# PCB.net
KiCad netlist of a schematic drawn in EAGLE
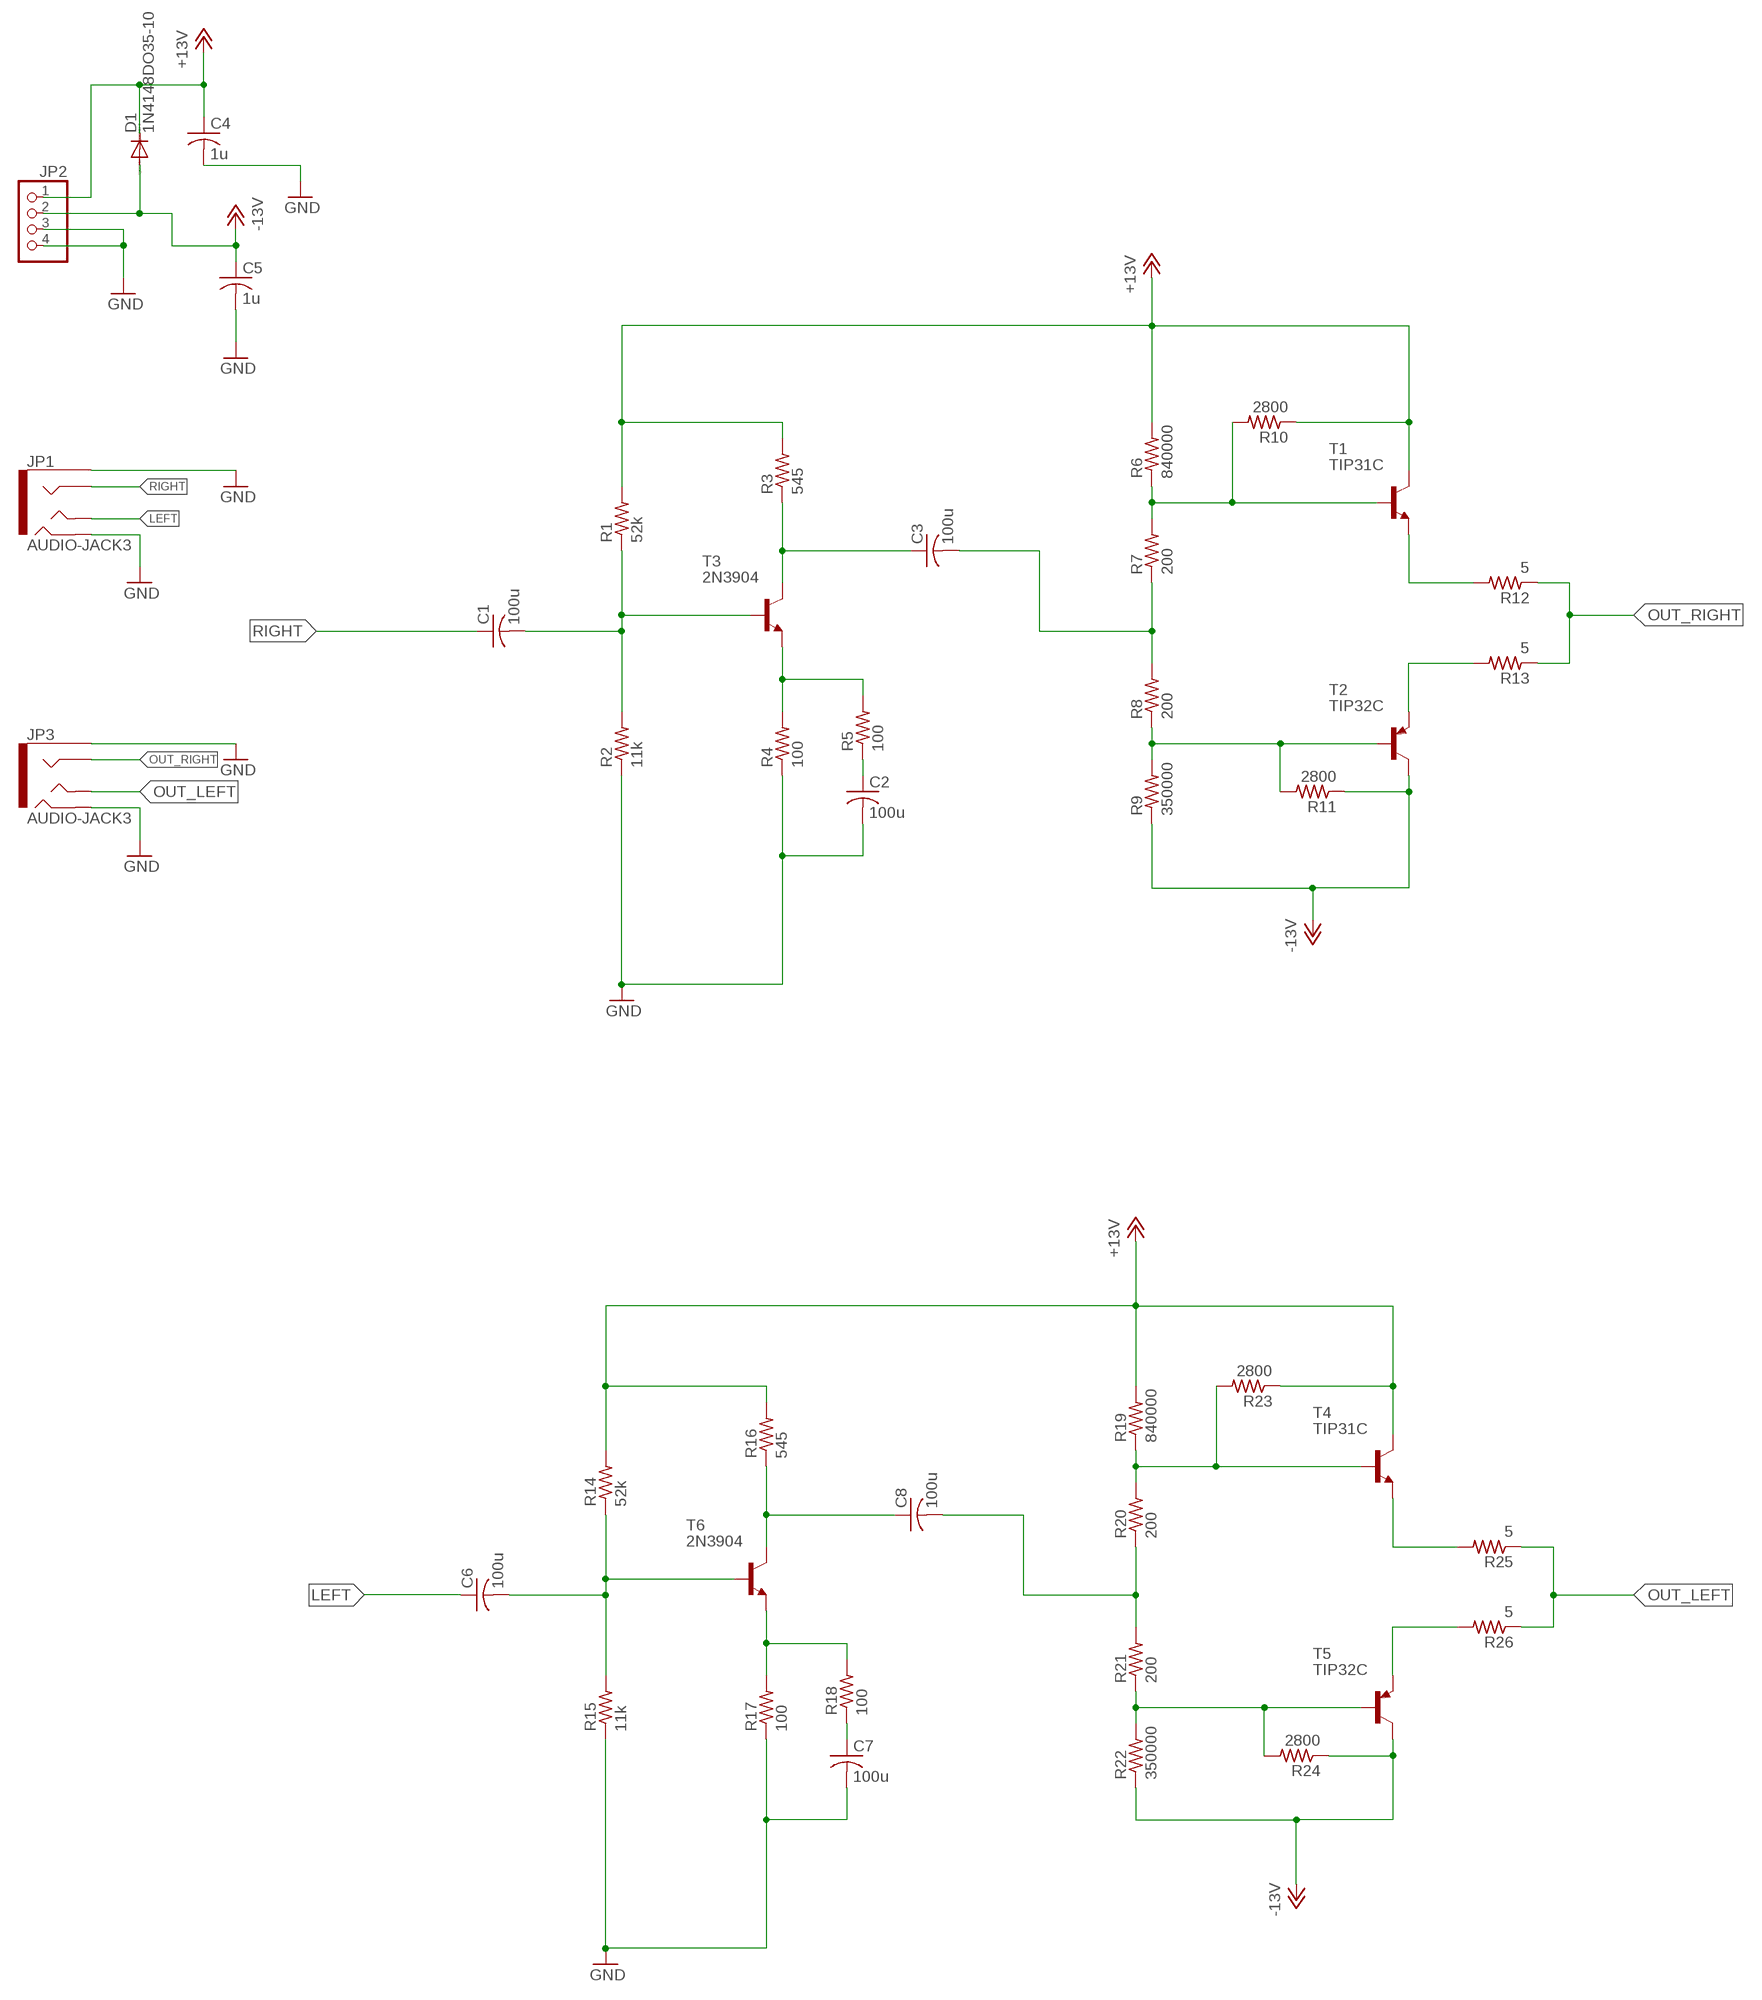
[diagram p0: schematic, sheet 1]

(export (version "E")
  (design (tool "Eeschema 10.0.6"))
  (components
    (comp (ref "C1")
      (value "100u")
      (footprint "eagle-import:C025-024X044")
      (libsource (lib "eagle-import") (part "C-US025-024X044"))
    )
    (comp (ref "C2")
      (value "100u")
      (footprint "eagle-import:C025-024X044")
      (libsource (lib "eagle-import") (part "C-US025-024X044"))
    )
    (comp (ref "C3")
      (value "100u")
      (footprint "eagle-import:C025-024X044")
      (libsource (lib "eagle-import") (part "C-US025-024X044"))
    )
    (comp (ref "C4")
      (value "1u")
      (footprint "eagle-import:C025-024X044")
      (libsource (lib "eagle-import") (part "C-US025-024X044"))
    )
    (comp (ref "C5")
      (value "1u")
      (footprint "eagle-import:C025-024X044")
      (libsource (lib "eagle-import") (part "C-US025-024X044"))
    )
    (comp (ref "C6")
      (value "100u")
      (footprint "eagle-import:C025-024X044")
      (libsource (lib "eagle-import") (part "C-US025-024X044"))
    )
    (comp (ref "C7")
      (value "100u")
      (footprint "eagle-import:C025-024X044")
      (libsource (lib "eagle-import") (part "C-US025-024X044"))
    )
    (comp (ref "C8")
      (value "100u")
      (footprint "eagle-import:C025-024X044")
      (libsource (lib "eagle-import") (part "C-US025-024X044"))
    )
    (comp (ref "D1")
      (value "1N4148DO35-10")
      (footprint "eagle-import:DO35-10")
      (libsource (lib "eagle-import") (part "1N4148DO35-10"))
    )
    (comp (ref "JP1")
      (value "AUDIO-JACK3")
      (footprint "eagle-import:AUDIO-JACK-TRRS-SMD")
      (libsource (lib "eagle-import") (part "AUDIO-JACK3"))
    )
    (comp (ref "JP2")
      (value "PINHD-1X4")
      (footprint "eagle-import:1X04")
      (libsource (lib "eagle-import") (part "PINHD-1X4"))
    )
    (comp (ref "JP3")
      (value "AUDIO-JACK3")
      (footprint "eagle-import:AUDIO-JACK-TRRS-SMD")
      (libsource (lib "eagle-import") (part "AUDIO-JACK3"))
    )
    (comp (ref "R1")
      (value "52k")
      (footprint "eagle-import:0204V")
      (libsource (lib "eagle-import") (part "R-US_0204/2V"))
    )
    (comp (ref "R2")
      (value "11k")
      (footprint "eagle-import:0204V")
      (libsource (lib "eagle-import") (part "R-US_0204/2V"))
    )
    (comp (ref "R3")
      (value "545")
      (footprint "eagle-import:0204V")
      (libsource (lib "eagle-import") (part "R-US_0204/2V"))
    )
    (comp (ref "R4")
      (value "100")
      (footprint "eagle-import:0204V")
      (libsource (lib "eagle-import") (part "R-US_0204/2V"))
    )
    (comp (ref "R5")
      (value "100")
      (footprint "eagle-import:0204V")
      (libsource (lib "eagle-import") (part "R-US_0204/2V"))
    )
    (comp (ref "R6")
      (value "840000")
      (footprint "eagle-import:0204V")
      (libsource (lib "eagle-import") (part "R-US_0204/2V"))
    )
    (comp (ref "R7")
      (value "200")
      (footprint "eagle-import:0204V")
      (libsource (lib "eagle-import") (part "R-US_0204/2V"))
    )
    (comp (ref "R8")
      (value "200")
      (footprint "eagle-import:0204V")
      (libsource (lib "eagle-import") (part "R-US_0204/2V"))
    )
    (comp (ref "R9")
      (value "350000")
      (footprint "eagle-import:0204V")
      (libsource (lib "eagle-import") (part "R-US_0204/2V"))
    )
    (comp (ref "R10")
      (value "2800")
      (footprint "eagle-import:0204V")
      (libsource (lib "eagle-import") (part "R-US_0204/2V"))
    )
    (comp (ref "R11")
      (value "2800")
      (footprint "eagle-import:0204V")
      (libsource (lib "eagle-import") (part "R-US_0204/2V"))
    )
    (comp (ref "R12")
      (value "5")
      (footprint "eagle-import:0204V")
      (libsource (lib "eagle-import") (part "R-US_0204/2V"))
    )
    (comp (ref "R13")
      (value "5")
      (footprint "eagle-import:0204V")
      (libsource (lib "eagle-import") (part "R-US_0204/2V"))
    )
    (comp (ref "R14")
      (value "52k")
      (footprint "eagle-import:0204V")
      (libsource (lib "eagle-import") (part "R-US_0204/2V"))
    )
    (comp (ref "R15")
      (value "11k")
      (footprint "eagle-import:0204V")
      (libsource (lib "eagle-import") (part "R-US_0204/2V"))
    )
    (comp (ref "R16")
      (value "545")
      (footprint "eagle-import:0204V")
      (libsource (lib "eagle-import") (part "R-US_0204/2V"))
    )
    (comp (ref "R17")
      (value "100")
      (footprint "eagle-import:0204V")
      (libsource (lib "eagle-import") (part "R-US_0204/2V"))
    )
    (comp (ref "R18")
      (value "100")
      (footprint "eagle-import:0204V")
      (libsource (lib "eagle-import") (part "R-US_0204/2V"))
    )
    (comp (ref "R19")
      (value "840000")
      (footprint "eagle-import:0204V")
      (libsource (lib "eagle-import") (part "R-US_0204/2V"))
    )
    (comp (ref "R20")
      (value "200")
      (footprint "eagle-import:0204V")
      (libsource (lib "eagle-import") (part "R-US_0204/2V"))
    )
    (comp (ref "R21")
      (value "200")
      (footprint "eagle-import:0204V")
      (libsource (lib "eagle-import") (part "R-US_0204/2V"))
    )
    (comp (ref "R22")
      (value "350000")
      (footprint "eagle-import:0204V")
      (libsource (lib "eagle-import") (part "R-US_0204/2V"))
    )
    (comp (ref "R23")
      (value "2800")
      (footprint "eagle-import:0204V")
      (libsource (lib "eagle-import") (part "R-US_0204/2V"))
    )
    (comp (ref "R24")
      (value "2800")
      (footprint "eagle-import:0204V")
      (libsource (lib "eagle-import") (part "R-US_0204/2V"))
    )
    (comp (ref "R25")
      (value "5")
      (footprint "eagle-import:0204V")
      (libsource (lib "eagle-import") (part "R-US_0204/2V"))
    )
    (comp (ref "R26")
      (value "5")
      (footprint "eagle-import:0204V")
      (libsource (lib "eagle-import") (part "R-US_0204/2V"))
    )
    (comp (ref "T1")
      (value "TIP31C")
      (footprint "eagle-import:TO220")
      (libsource (lib "eagle-import") (part "TIP31C"))
    )
    (comp (ref "T2")
      (value "TIP32C")
      (footprint "eagle-import:TO220")
      (libsource (lib "eagle-import") (part "TIP32C"))
    )
    (comp (ref "T3")
      (value "2N3904")
      (footprint "eagle-import:TO92")
      (libsource (lib "eagle-import") (part "2N3904"))
    )
    (comp (ref "T4")
      (value "TIP31C")
      (footprint "eagle-import:TO220")
      (libsource (lib "eagle-import") (part "TIP31C"))
    )
    (comp (ref "T5")
      (value "TIP32C")
      (footprint "eagle-import:TO220")
      (libsource (lib "eagle-import") (part "TIP32C"))
    )
    (comp (ref "T6")
      (value "2N3904")
      (footprint "eagle-import:TO92")
      (libsource (lib "eagle-import") (part "2N3904"))
    )
  )
  (nets
    (net (code "1") (name "+13V") (class "Default")
      (node (ref "C4") (pin "1") (pinfunction "1_1") (pintype "passive"))
      (node (ref "D1") (pin "C") (pinfunction "C_C") (pintype "passive"))
      (node (ref "JP2") (pin "1") (pinfunction "1_1") (pintype "passive"))
      (node (ref "R1") (pin "2") (pinfunction "2_2") (pintype "passive"))
      (node (ref "R10") (pin "1") (pinfunction "1_1") (pintype "passive"))
      (node (ref "R14") (pin "2") (pinfunction "2_2") (pintype "passive"))
      (node (ref "R16") (pin "2") (pinfunction "2_2") (pintype "passive"))
      (node (ref "R19") (pin "2") (pinfunction "2_2") (pintype "passive"))
      (node (ref "R23") (pin "1") (pinfunction "1_1") (pintype "passive"))
      (node (ref "R3") (pin "2") (pinfunction "2_2") (pintype "passive"))
      (node (ref "R6") (pin "2") (pinfunction "2_2") (pintype "passive"))
      (node (ref "T1") (pin "2") (pinfunction "C_2") (pintype "passive"))
      (node (ref "T4") (pin "2") (pinfunction "C_2") (pintype "passive"))
    )
    (net (code "2") (name "-13V") (class "Default")
      (node (ref "C5") (pin "1") (pinfunction "1_1") (pintype "passive"))
      (node (ref "D1") (pin "A") (pinfunction "A_A") (pintype "passive"))
      (node (ref "JP2") (pin "2") (pinfunction "2_2") (pintype "passive"))
      (node (ref "R11") (pin "1") (pinfunction "1_1") (pintype "passive"))
      (node (ref "R22") (pin "1") (pinfunction "1_1") (pintype "passive"))
      (node (ref "R24") (pin "1") (pinfunction "1_1") (pintype "passive"))
      (node (ref "R9") (pin "1") (pinfunction "1_1") (pintype "passive"))
      (node (ref "T2") (pin "2") (pinfunction "C_2") (pintype "passive"))
      (node (ref "T5") (pin "2") (pinfunction "C_2") (pintype "passive"))
    )
    (net (code "3") (name "GND") (class "Default")
      (node (ref "C2") (pin "2") (pinfunction "2_2") (pintype "passive"))
      (node (ref "C4") (pin "2") (pinfunction "2_2") (pintype "passive"))
      (node (ref "C5") (pin "2") (pinfunction "2_2") (pintype "passive"))
      (node (ref "C7") (pin "2") (pinfunction "2_2") (pintype "passive"))
      (node (ref "JP1") (pin "EARTH") (pinfunction "EARTH_EARTH") (pintype "bidirectional"))
      (node (ref "JP1") (pin "RING2") (pinfunction "RING2_RING2") (pintype "bidirectional"))
      (node (ref "JP2") (pin "3") (pinfunction "3_3") (pintype "passive"))
      (node (ref "JP2") (pin "4") (pinfunction "4_4") (pintype "passive"))
      (node (ref "JP3") (pin "EARTH") (pinfunction "EARTH_EARTH") (pintype "bidirectional"))
      (node (ref "JP3") (pin "RING2") (pinfunction "RING2_RING2") (pintype "bidirectional"))
      (node (ref "R15") (pin "1") (pinfunction "1_1") (pintype "passive"))
      (node (ref "R17") (pin "1") (pinfunction "1_1") (pintype "passive"))
      (node (ref "R2") (pin "1") (pinfunction "1_1") (pintype "passive"))
      (node (ref "R4") (pin "1") (pinfunction "1_1") (pintype "passive"))
    )
    (net (code "4") (name "LEFT") (class "Default")
      (node (ref "C6") (pin "1") (pinfunction "1_1") (pintype "passive"))
      (node (ref "JP1") (pin "TIP") (pinfunction "TIP_TIP") (pintype "bidirectional"))
    )
    (net (code "5") (name "Net-(C2-Pad1)") (class "Default")
      (node (ref "C2") (pin "1") (pinfunction "1_1") (pintype "passive"))
      (node (ref "R5") (pin "1") (pinfunction "1_1") (pintype "passive"))
    )
    (net (code "6") (name "Net-(C3-Pad2)") (class "Default")
      (node (ref "C3") (pin "2") (pinfunction "2_2") (pintype "passive"))
      (node (ref "R7") (pin "1") (pinfunction "1_1") (pintype "passive"))
      (node (ref "R8") (pin "2") (pinfunction "2_2") (pintype "passive"))
    )
    (net (code "7") (name "Net-(C7-Pad1)") (class "Default")
      (node (ref "C7") (pin "1") (pinfunction "1_1") (pintype "passive"))
      (node (ref "R18") (pin "1") (pinfunction "1_1") (pintype "passive"))
    )
    (net (code "8") (name "Net-(C8-Pad2)") (class "Default")
      (node (ref "C8") (pin "2") (pinfunction "2_2") (pintype "passive"))
      (node (ref "R20") (pin "1") (pinfunction "1_1") (pintype "passive"))
      (node (ref "R21") (pin "2") (pinfunction "2_2") (pintype "passive"))
    )
    (net (code "9") (name "Net-(T1-B)") (class "Default")
      (node (ref "R10") (pin "2") (pinfunction "2_2") (pintype "passive"))
      (node (ref "R6") (pin "1") (pinfunction "1_1") (pintype "passive"))
      (node (ref "R7") (pin "2") (pinfunction "2_2") (pintype "passive"))
      (node (ref "T1") (pin "1") (pinfunction "B_1") (pintype "passive"))
    )
    (net (code "10") (name "Net-(T1-E)") (class "Default")
      (node (ref "R12") (pin "2") (pinfunction "2_2") (pintype "passive"))
      (node (ref "T1") (pin "3") (pinfunction "E_3") (pintype "passive"))
    )
    (net (code "11") (name "Net-(T2-B)") (class "Default")
      (node (ref "R11") (pin "2") (pinfunction "2_2") (pintype "passive"))
      (node (ref "R8") (pin "1") (pinfunction "1_1") (pintype "passive"))
      (node (ref "R9") (pin "2") (pinfunction "2_2") (pintype "passive"))
      (node (ref "T2") (pin "1") (pinfunction "B_1") (pintype "passive"))
    )
    (net (code "12") (name "Net-(T2-E)") (class "Default")
      (node (ref "R13") (pin "2") (pinfunction "2_2") (pintype "passive"))
      (node (ref "T2") (pin "3") (pinfunction "E_3") (pintype "passive"))
    )
    (net (code "13") (name "Net-(T3-B)") (class "Default")
      (node (ref "C1") (pin "2") (pinfunction "2_2") (pintype "passive"))
      (node (ref "R1") (pin "1") (pinfunction "1_1") (pintype "passive"))
      (node (ref "R2") (pin "2") (pinfunction "2_2") (pintype "passive"))
      (node (ref "T3") (pin "2") (pinfunction "B_2") (pintype "passive"))
    )
    (net (code "14") (name "Net-(T3-C)") (class "Default")
      (node (ref "C3") (pin "1") (pinfunction "1_1") (pintype "passive"))
      (node (ref "R3") (pin "1") (pinfunction "1_1") (pintype "passive"))
      (node (ref "T3") (pin "1") (pinfunction "C_1") (pintype "passive"))
    )
    (net (code "15") (name "Net-(T3-E)") (class "Default")
      (node (ref "R4") (pin "2") (pinfunction "2_2") (pintype "passive"))
      (node (ref "R5") (pin "2") (pinfunction "2_2") (pintype "passive"))
      (node (ref "T3") (pin "3") (pinfunction "E_3") (pintype "passive"))
    )
    (net (code "16") (name "Net-(T4-B)") (class "Default")
      (node (ref "R19") (pin "1") (pinfunction "1_1") (pintype "passive"))
      (node (ref "R20") (pin "2") (pinfunction "2_2") (pintype "passive"))
      (node (ref "R23") (pin "2") (pinfunction "2_2") (pintype "passive"))
      (node (ref "T4") (pin "1") (pinfunction "B_1") (pintype "passive"))
    )
    (net (code "17") (name "Net-(T4-E)") (class "Default")
      (node (ref "R25") (pin "2") (pinfunction "2_2") (pintype "passive"))
      (node (ref "T4") (pin "3") (pinfunction "E_3") (pintype "passive"))
    )
    (net (code "18") (name "Net-(T5-B)") (class "Default")
      (node (ref "R21") (pin "1") (pinfunction "1_1") (pintype "passive"))
      (node (ref "R22") (pin "2") (pinfunction "2_2") (pintype "passive"))
      (node (ref "R24") (pin "2") (pinfunction "2_2") (pintype "passive"))
      (node (ref "T5") (pin "1") (pinfunction "B_1") (pintype "passive"))
    )
    (net (code "19") (name "Net-(T5-E)") (class "Default")
      (node (ref "R26") (pin "2") (pinfunction "2_2") (pintype "passive"))
      (node (ref "T5") (pin "3") (pinfunction "E_3") (pintype "passive"))
    )
    (net (code "20") (name "Net-(T6-B)") (class "Default")
      (node (ref "C6") (pin "2") (pinfunction "2_2") (pintype "passive"))
      (node (ref "R14") (pin "1") (pinfunction "1_1") (pintype "passive"))
      (node (ref "R15") (pin "2") (pinfunction "2_2") (pintype "passive"))
      (node (ref "T6") (pin "2") (pinfunction "B_2") (pintype "passive"))
    )
    (net (code "21") (name "Net-(T6-C)") (class "Default")
      (node (ref "C8") (pin "1") (pinfunction "1_1") (pintype "passive"))
      (node (ref "R16") (pin "1") (pinfunction "1_1") (pintype "passive"))
      (node (ref "T6") (pin "1") (pinfunction "C_1") (pintype "passive"))
    )
    (net (code "22") (name "Net-(T6-E)") (class "Default")
      (node (ref "R17") (pin "2") (pinfunction "2_2") (pintype "passive"))
      (node (ref "R18") (pin "2") (pinfunction "2_2") (pintype "passive"))
      (node (ref "T6") (pin "3") (pinfunction "E_3") (pintype "passive"))
    )
    (net (code "23") (name "OUT_LEFT") (class "Default")
      (node (ref "JP3") (pin "TIP") (pinfunction "TIP_TIP") (pintype "bidirectional"))
      (node (ref "R25") (pin "1") (pinfunction "1_1") (pintype "passive"))
      (node (ref "R26") (pin "1") (pinfunction "1_1") (pintype "passive"))
    )
    (net (code "24") (name "OUT_RIGHT") (class "Default")
      (node (ref "JP3") (pin "RING1") (pinfunction "RING1_RING1") (pintype "bidirectional"))
      (node (ref "R12") (pin "1") (pinfunction "1_1") (pintype "passive"))
      (node (ref "R13") (pin "1") (pinfunction "1_1") (pintype "passive"))
    )
    (net (code "25") (name "RIGHT") (class "Default")
      (node (ref "C1") (pin "1") (pinfunction "1_1") (pintype "passive"))
      (node (ref "JP1") (pin "RING1") (pinfunction "RING1_RING1") (pintype "bidirectional"))
    )
  )
)
